# PCB-DISPARRAY4c.net
KiCad netlist of a schematic drawn in EAGLE
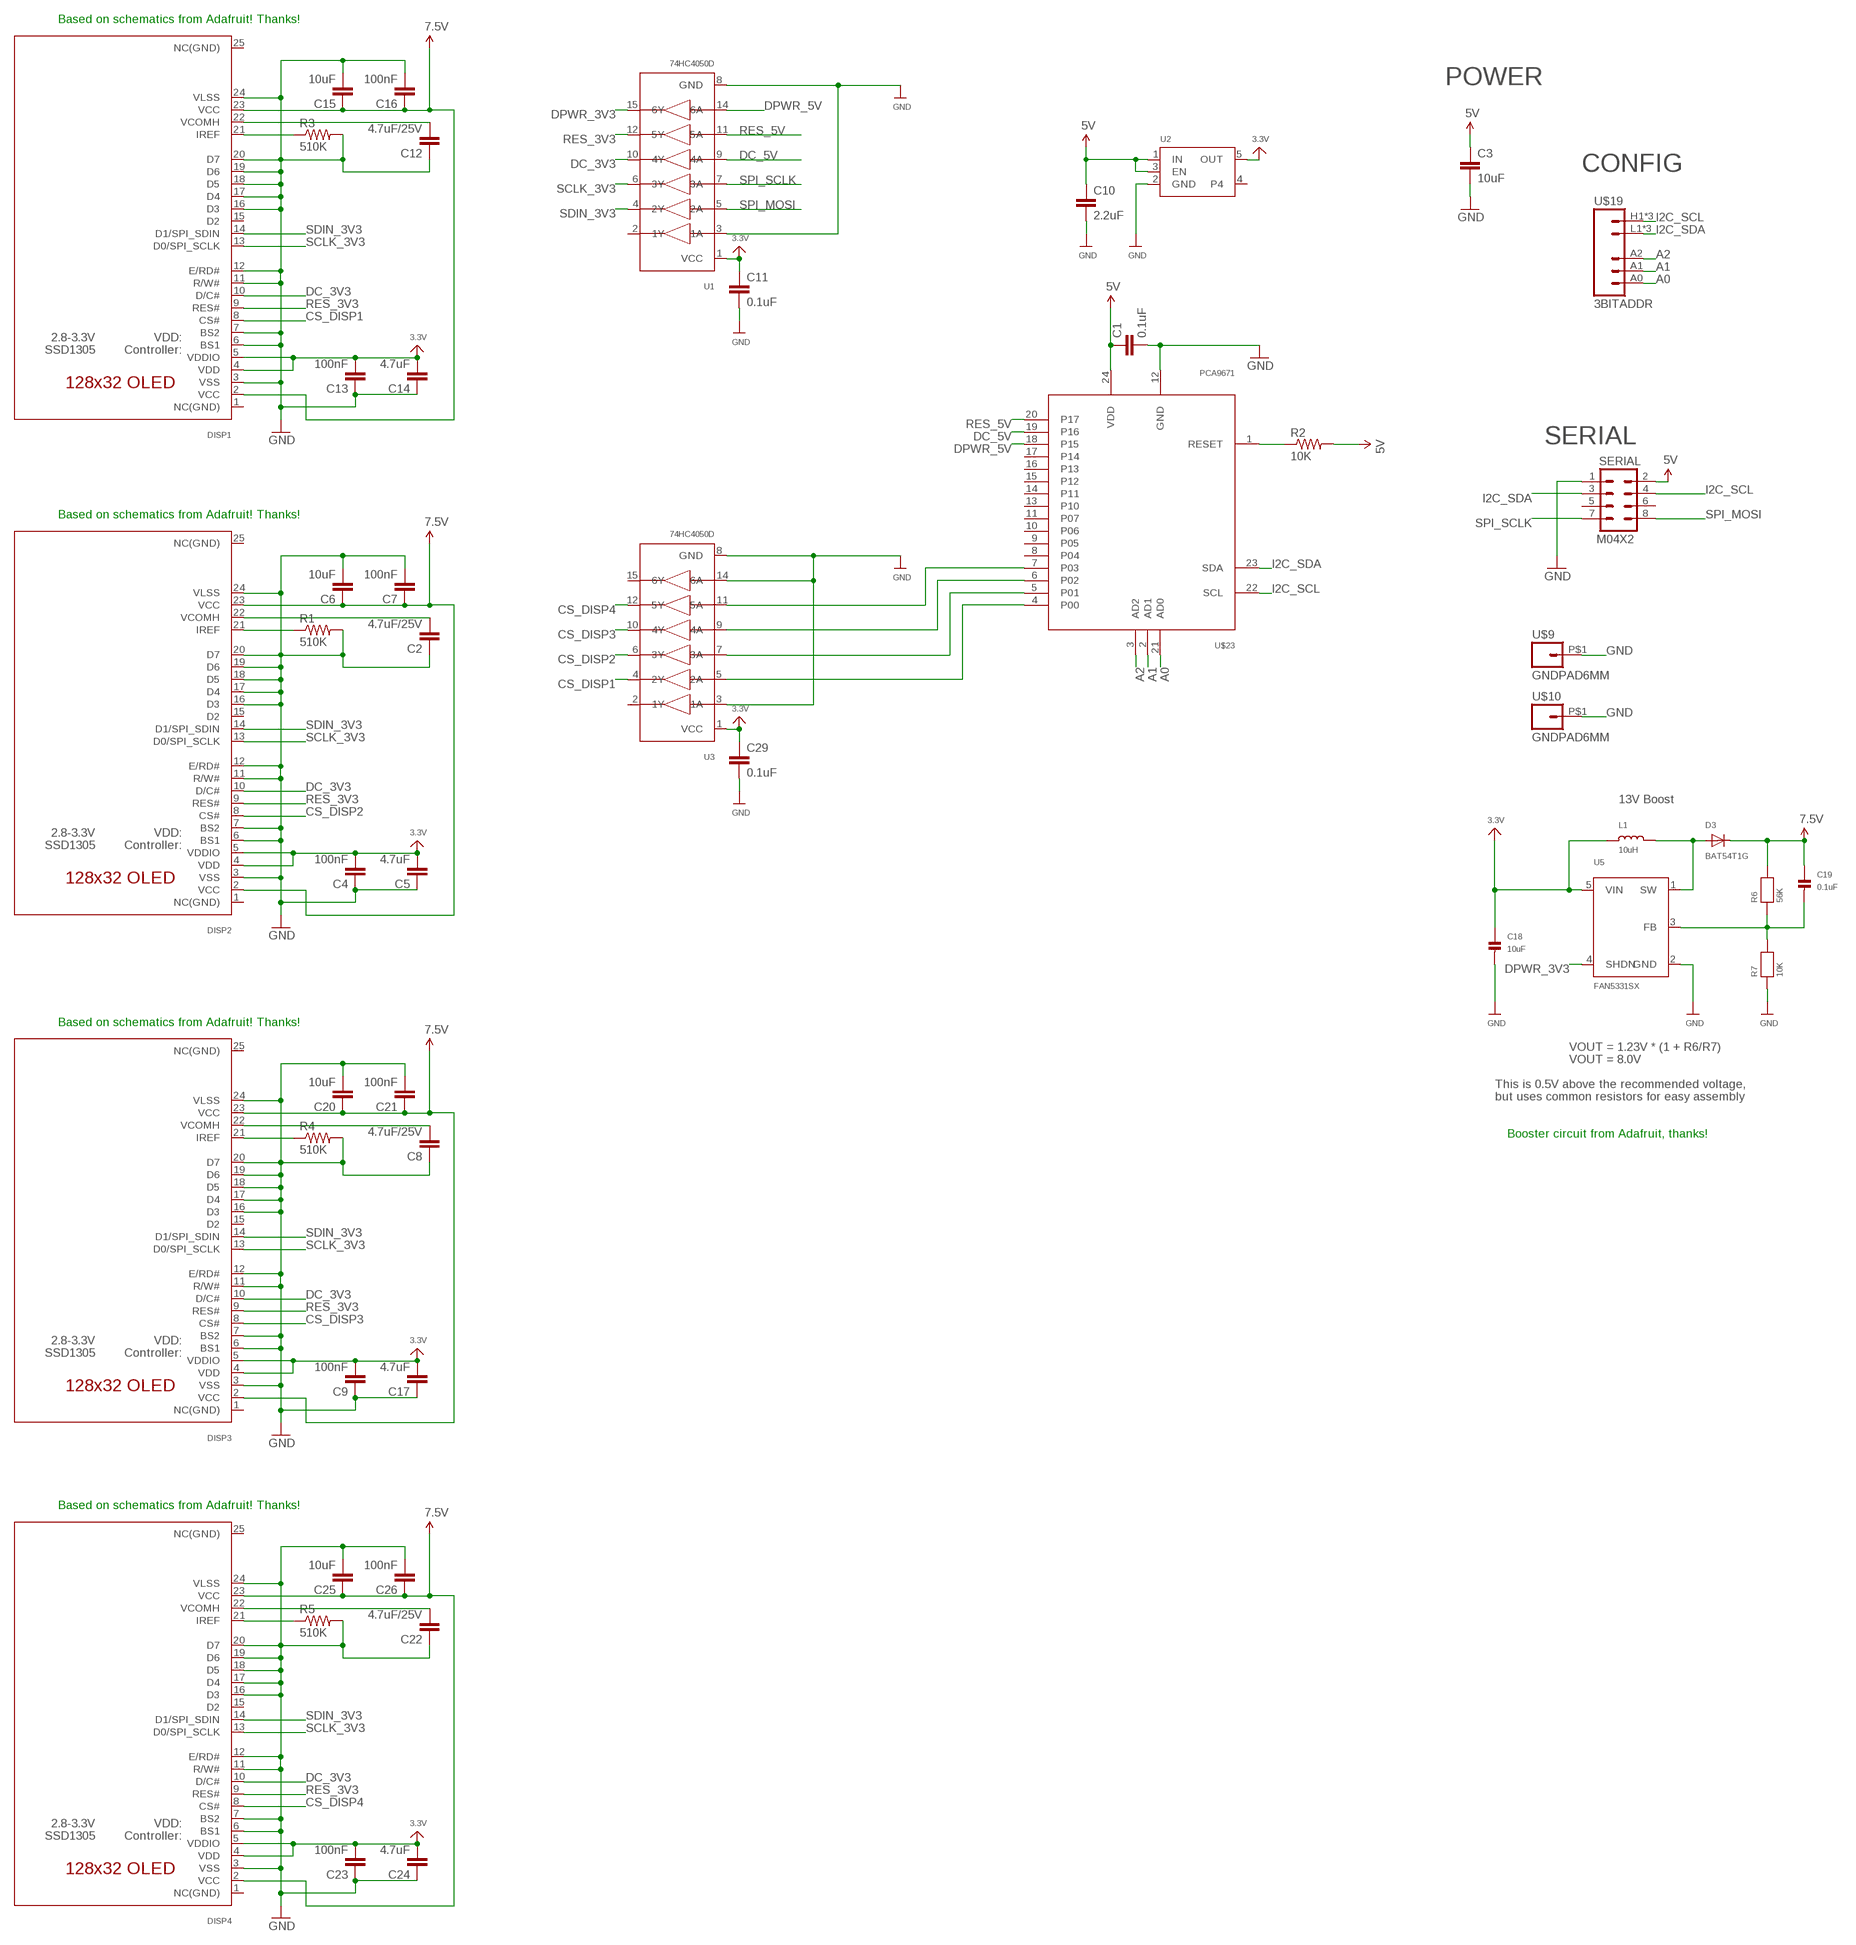
[diagram p0: schematic, sheet 1]

(export (version "E")
  (design (tool "Eeschema 10.0.6"))
  (components
    (comp (ref "C1")
      (value "0.1uF")
      (footprint "eagle-import:0603-CAP")
      (libsource (lib "eagle-import") (part "CAP0603-CAP"))
    )
    (comp (ref "C2")
      (value "4.7uF/25V")
      (footprint "eagle-import:0805")
      (libsource (lib "eagle-import") (part "CAP0805"))
    )
    (comp (ref "C3")
      (value "10uF")
      (footprint "eagle-import:0805")
      (libsource (lib "eagle-import") (part "CAP0805"))
    )
    (comp (ref "C4")
      (value "100nF")
      (footprint "eagle-import:0603-CAP")
      (libsource (lib "eagle-import") (part "CAP0603-CAP"))
    )
    (comp (ref "C5")
      (value "4.7uF")
      (footprint "eagle-import:0603-CAP")
      (libsource (lib "eagle-import") (part "CAP0603-CAP"))
    )
    (comp (ref "C6")
      (value "10uF")
      (footprint "eagle-import:0805")
      (libsource (lib "eagle-import") (part "CAP0805"))
    )
    (comp (ref "C7")
      (value "100nF")
      (footprint "eagle-import:0805")
      (libsource (lib "eagle-import") (part "CAP0805"))
    )
    (comp (ref "C8")
      (value "4.7uF/25V")
      (footprint "eagle-import:0805")
      (libsource (lib "eagle-import") (part "CAP0805"))
    )
    (comp (ref "C9")
      (value "100nF")
      (footprint "eagle-import:0603-CAP")
      (libsource (lib "eagle-import") (part "CAP0603-CAP"))
    )
    (comp (ref "C10")
      (value "2.2uF")
      (footprint "eagle-import:0603-CAP")
      (libsource (lib "eagle-import") (part "CAP0603-CAP"))
    )
    (comp (ref "C11")
      (value "0.1uF")
      (footprint "eagle-import:0603-CAP")
      (libsource (lib "eagle-import") (part "CAP0603-CAP"))
    )
    (comp (ref "C12")
      (value "4.7uF/25V")
      (footprint "eagle-import:0805")
      (libsource (lib "eagle-import") (part "CAP0805"))
    )
    (comp (ref "C13")
      (value "100nF")
      (footprint "eagle-import:0603-CAP")
      (libsource (lib "eagle-import") (part "CAP0603-CAP"))
    )
    (comp (ref "C14")
      (value "4.7uF")
      (footprint "eagle-import:0603-CAP")
      (libsource (lib "eagle-import") (part "CAP0603-CAP"))
    )
    (comp (ref "C15")
      (value "10uF")
      (footprint "eagle-import:0805")
      (libsource (lib "eagle-import") (part "CAP0805"))
    )
    (comp (ref "C16")
      (value "100nF")
      (footprint "eagle-import:0603-CAP")
      (libsource (lib "eagle-import") (part "CAP0603-CAP"))
    )
    (comp (ref "C17")
      (value "4.7uF")
      (footprint "eagle-import:0603-CAP")
      (libsource (lib "eagle-import") (part "CAP0603-CAP"))
    )
    (comp (ref "C18")
      (value "10uF")
      (footprint "eagle-import:0805")
      (libsource (lib "eagle-import") (part "CAP_CERAMIC0805"))
    )
    (comp (ref "C19")
      (value "0.1uF")
      (footprint "eagle-import:0603")
      (libsource (lib "eagle-import") (part "CAP_CERAMIC0603"))
    )
    (comp (ref "C20")
      (value "10uF")
      (footprint "eagle-import:0805")
      (libsource (lib "eagle-import") (part "CAP0805"))
    )
    (comp (ref "C21")
      (value "100nF")
      (footprint "eagle-import:0603-CAP")
      (libsource (lib "eagle-import") (part "CAP0603-CAP"))
    )
    (comp (ref "C22")
      (value "4.7uF/25V")
      (footprint "eagle-import:0805")
      (libsource (lib "eagle-import") (part "CAP0805"))
    )
    (comp (ref "C23")
      (value "100nF")
      (footprint "eagle-import:0603-CAP")
      (libsource (lib "eagle-import") (part "CAP0603-CAP"))
    )
    (comp (ref "C24")
      (value "4.7uF")
      (footprint "eagle-import:0603-CAP")
      (libsource (lib "eagle-import") (part "CAP0603-CAP"))
    )
    (comp (ref "C25")
      (value "10uF")
      (footprint "eagle-import:0805")
      (libsource (lib "eagle-import") (part "CAP0805"))
    )
    (comp (ref "C26")
      (value "100nF")
      (footprint "eagle-import:0603-CAP")
      (libsource (lib "eagle-import") (part "CAP0603-CAP"))
    )
    (comp (ref "C29")
      (value "0.1uF")
      (footprint "eagle-import:0603-CAP")
      (libsource (lib "eagle-import") (part "CAP0603-CAP"))
    )
    (comp (ref "D3")
      (value "BAT54T1G")
      (footprint "eagle-import:SOD-123")
      (libsource (lib "eagle-import") (part "DIODESOD-123"))
    )
    (comp (ref "DISP1")
      (value "ER-OLED0.91-2TOP")
      (footprint "eagle-import:ER_OLED0.91-2")
      (libsource (lib "eagle-import") (part "ER-OLED0.91-2TOP"))
    )
    (comp (ref "DISP2")
      (value "ER-OLED0.91-2TOP")
      (footprint "eagle-import:ER_OLED0.91-2")
      (libsource (lib "eagle-import") (part "ER-OLED0.91-2TOP"))
    )
    (comp (ref "DISP3")
      (value "ER-OLED0.91-2TOP")
      (footprint "eagle-import:ER_OLED0.91-2")
      (libsource (lib "eagle-import") (part "ER-OLED0.91-2TOP"))
    )
    (comp (ref "DISP4")
      (value "ER-OLED0.91-2TOP")
      (footprint "eagle-import:ER_OLED0.91-2")
      (libsource (lib "eagle-import") (part "ER-OLED0.91-2TOP"))
    )
    (comp (ref "L1")
      (value "10uH")
      (footprint "eagle-import:INDUCTOR_1007")
      (libsource (lib "eagle-import") (part "INDUCTOR"))
    )
    (comp (ref "R1")
      (value "510K")
      (footprint "eagle-import:0603-RES")
      (libsource (lib "eagle-import") (part "RESISTOR0603-RES"))
    )
    (comp (ref "R2")
      (value "10K")
      (footprint "eagle-import:0603-RES")
      (libsource (lib "eagle-import") (part "RESISTOR0603-RES"))
    )
    (comp (ref "R3")
      (value "510K")
      (footprint "eagle-import:0603-RES")
      (libsource (lib "eagle-import") (part "RESISTOR0603-RES"))
    )
    (comp (ref "R4")
      (value "510K")
      (footprint "eagle-import:0603-RES")
      (libsource (lib "eagle-import") (part "RESISTOR0603-RES"))
    )
    (comp (ref "R5")
      (value "510K")
      (footprint "eagle-import:0603-RES")
      (libsource (lib "eagle-import") (part "RESISTOR0603-RES"))
    )
    (comp (ref "R6")
      (value "56K")
      (footprint "eagle-import:0603")
      (libsource (lib "eagle-import") (part "RESISTOR0603"))
    )
    (comp (ref "R7")
      (value "10K")
      (footprint "eagle-import:0603")
      (libsource (lib "eagle-import") (part "RESISTOR0603"))
    )
    (comp (ref "SERIAL")
      (value "M04X2")
      (footprint "eagle-import:2X4")
      (libsource (lib "eagle-import") (part "M04X2"))
    )
    (comp (ref "U$9")
      (value "GNDPAD6MM")
      (footprint "eagle-import:3.2MMPAD6MM")
      (libsource (lib "eagle-import") (part "GNDPAD6MM"))
    )
    (comp (ref "U$10")
      (value "GNDPAD6MM")
      (footprint "eagle-import:3.2MMPAD6MM")
      (libsource (lib "eagle-import") (part "GNDPAD6MM"))
    )
    (comp (ref "U$19")
      (value "3BITADDR")
      (footprint "eagle-import:3BITADDR")
      (libsource (lib "eagle-import") (part "3BITADDR"))
    )
    (comp (ref "U$23")
      (value "PCA9671")
      (footprint "eagle-import:TSSOP24")
      (libsource (lib "eagle-import") (part "PCA9671"))
    )
    (comp (ref "U1")
      (value "74HC4050D")
      (footprint "eagle-import:TSSOP16")
      (libsource (lib "eagle-import") (part "74HC4050DTSSOP16"))
    )
    (comp (ref "U2")
      (value "VREG_SOT23-5")
      (footprint "eagle-import:SOT23-5")
      (libsource (lib "eagle-import") (part "VREG_SOT23-5"))
    )
    (comp (ref "U3")
      (value "74HC4050D")
      (footprint "eagle-import:TSSOP16")
      (libsource (lib "eagle-import") (part "74HC4050DTSSOP16"))
    )
    (comp (ref "U5")
      (value "FAN5331SX")
      (footprint "eagle-import:SOT23-5")
      (libsource (lib "eagle-import") (part "FAN5331"))
    )
  )
  (nets
    (net (code "1") (name "3.3V") (class "Default")
      (node (ref "C11") (pin "1") (pinfunction "1_1") (pintype "passive"))
      (node (ref "C13") (pin "2") (pinfunction "2_2") (pintype "passive"))
      (node (ref "C14") (pin "2") (pinfunction "2_2") (pintype "passive"))
      (node (ref "C17") (pin "2") (pinfunction "2_2") (pintype "passive"))
      (node (ref "C18") (pin "1") (pinfunction "P$1_1") (pintype "passive"))
      (node (ref "C23") (pin "2") (pinfunction "2_2") (pintype "passive"))
      (node (ref "C24") (pin "2") (pinfunction "2_2") (pintype "passive"))
      (node (ref "C29") (pin "1") (pinfunction "1_1") (pintype "passive"))
      (node (ref "C4") (pin "2") (pinfunction "2_2") (pintype "passive"))
      (node (ref "C5") (pin "2") (pinfunction "2_2") (pintype "passive"))
      (node (ref "C9") (pin "2") (pinfunction "2_2") (pintype "passive"))
      (node (ref "DISP1") (pin "4") (pinfunction "VDD_4") (pintype "power_in"))
      (node (ref "DISP1") (pin "5") (pinfunction "VDDIO_5") (pintype "power_in"))
      (node (ref "DISP2") (pin "4") (pinfunction "VDD_4") (pintype "power_in"))
      (node (ref "DISP2") (pin "5") (pinfunction "VDDIO_5") (pintype "power_in"))
      (node (ref "DISP3") (pin "4") (pinfunction "VDD_4") (pintype "power_in"))
      (node (ref "DISP3") (pin "5") (pinfunction "VDDIO_5") (pintype "power_in"))
      (node (ref "DISP4") (pin "4") (pinfunction "VDD_4") (pintype "power_in"))
      (node (ref "DISP4") (pin "5") (pinfunction "VDDIO_5") (pintype "power_in"))
      (node (ref "L1") (pin "P$1") (pinfunction "1_P$1") (pintype "passive"))
      (node (ref "U1") (pin "1") (pinfunction "VCC_1") (pintype "bidirectional"))
      (node (ref "U2") (pin "5") (pinfunction "OUT_5") (pintype "bidirectional"))
      (node (ref "U3") (pin "1") (pinfunction "VCC_1") (pintype "bidirectional"))
      (node (ref "U5") (pin "5") (pinfunction "VIN_5") (pintype "bidirectional"))
    )
    (net (code "2") (name "5V") (class "Default")
      (node (ref "C1") (pin "1") (pinfunction "1_1") (pintype "passive"))
      (node (ref "C10") (pin "1") (pinfunction "1_1") (pintype "passive"))
      (node (ref "C3") (pin "1") (pinfunction "1_1") (pintype "passive"))
      (node (ref "R2") (pin "2") (pinfunction "2_2") (pintype "passive"))
      (node (ref "SERIAL") (pin "2") (pinfunction "2_2") (pintype "passive"))
      (node (ref "U$23") (pin "24") (pinfunction "VDD_24") (pintype "power_in"))
      (node (ref "U2") (pin "1") (pinfunction "IN_1") (pintype "bidirectional"))
      (node (ref "U2") (pin "3") (pinfunction "EN_3") (pintype "bidirectional"))
    )
    (net (code "3") (name "7.5V") (class "Default")
      (node (ref "C15") (pin "1") (pinfunction "1_1") (pintype "passive"))
      (node (ref "C16") (pin "1") (pinfunction "1_1") (pintype "passive"))
      (node (ref "C19") (pin "1") (pinfunction "P$1_1") (pintype "passive"))
      (node (ref "C20") (pin "1") (pinfunction "1_1") (pintype "passive"))
      (node (ref "C21") (pin "1") (pinfunction "1_1") (pintype "passive"))
      (node (ref "C25") (pin "1") (pinfunction "1_1") (pintype "passive"))
      (node (ref "C26") (pin "1") (pinfunction "1_1") (pintype "passive"))
      (node (ref "C6") (pin "1") (pinfunction "1_1") (pintype "passive"))
      (node (ref "C7") (pin "1") (pinfunction "1_1") (pintype "passive"))
      (node (ref "D3") (pin "C") (pinfunction "C_C") (pintype "passive"))
      (node (ref "DISP1") (pin "2") (pinfunction "VCC_2") (pintype "power_in"))
      (node (ref "DISP1") (pin "23") (pinfunction "VCC_23") (pintype "power_in"))
      (node (ref "DISP2") (pin "2") (pinfunction "VCC_2") (pintype "power_in"))
      (node (ref "DISP2") (pin "23") (pinfunction "VCC_23") (pintype "power_in"))
      (node (ref "DISP3") (pin "2") (pinfunction "VCC_2") (pintype "power_in"))
      (node (ref "DISP3") (pin "23") (pinfunction "VCC_23") (pintype "power_in"))
      (node (ref "DISP4") (pin "2") (pinfunction "VCC_2") (pintype "power_in"))
      (node (ref "DISP4") (pin "23") (pinfunction "VCC_23") (pintype "power_in"))
      (node (ref "R6") (pin "2") (pinfunction "2_2") (pintype "passive"))
    )
    (net (code "4") (name "A0") (class "Default")
      (node (ref "U$19") (pin "A0") (pinfunction "A0_A0") (pintype "passive"))
      (node (ref "U$23") (pin "21") (pinfunction "AD0_21") (pintype "input"))
    )
    (net (code "5") (name "A1") (class "Default")
      (node (ref "U$19") (pin "A1") (pinfunction "A1_A1") (pintype "passive"))
      (node (ref "U$23") (pin "2") (pinfunction "AD1_2") (pintype "input"))
    )
    (net (code "6") (name "A2") (class "Default")
      (node (ref "U$19") (pin "A2") (pinfunction "A2_A2") (pintype "passive"))
      (node (ref "U$23") (pin "3") (pinfunction "AD2_3") (pintype "input"))
    )
    (net (code "7") (name "CS_DISP1") (class "Default")
      (node (ref "DISP1") (pin "8") (pinfunction "CS#_8") (pintype "input"))
      (node (ref "U3") (pin "4") (pinfunction "2Y_4") (pintype "bidirectional"))
    )
    (net (code "8") (name "CS_DISP2") (class "Default")
      (node (ref "DISP2") (pin "8") (pinfunction "CS#_8") (pintype "input"))
      (node (ref "U3") (pin "6") (pinfunction "3Y_6") (pintype "bidirectional"))
    )
    (net (code "9") (name "CS_DISP3") (class "Default")
      (node (ref "DISP3") (pin "8") (pinfunction "CS#_8") (pintype "input"))
      (node (ref "U3") (pin "10") (pinfunction "4Y_10") (pintype "bidirectional"))
    )
    (net (code "10") (name "CS_DISP4") (class "Default")
      (node (ref "DISP4") (pin "8") (pinfunction "CS#_8") (pintype "input"))
      (node (ref "U3") (pin "12") (pinfunction "5Y_12") (pintype "bidirectional"))
    )
    (net (code "11") (name "DC_3V3") (class "Default")
      (node (ref "DISP1") (pin "10") (pinfunction "D/C#_10") (pintype "input"))
      (node (ref "DISP2") (pin "10") (pinfunction "D/C#_10") (pintype "input"))
      (node (ref "DISP3") (pin "10") (pinfunction "D/C#_10") (pintype "input"))
      (node (ref "DISP4") (pin "10") (pinfunction "D/C#_10") (pintype "input"))
      (node (ref "U1") (pin "10") (pinfunction "4Y_10") (pintype "bidirectional"))
    )
    (net (code "12") (name "DC_5V") (class "Default")
      (node (ref "U$23") (pin "19") (pinfunction "P16_19") (pintype "output"))
      (node (ref "U1") (pin "9") (pinfunction "4A_9") (pintype "bidirectional"))
    )
    (net (code "13") (name "DPWR_3V3") (class "Default")
      (node (ref "U1") (pin "15") (pinfunction "6Y_15") (pintype "bidirectional"))
      (node (ref "U5") (pin "4") (pinfunction "SHDN_4") (pintype "bidirectional"))
    )
    (net (code "14") (name "DPWR_5V") (class "Default")
      (node (ref "U$23") (pin "18") (pinfunction "P15_18") (pintype "output"))
      (node (ref "U1") (pin "14") (pinfunction "6A_14") (pintype "bidirectional"))
    )
    (net (code "15") (name "GND") (class "Default")
      (node (ref "C1") (pin "2") (pinfunction "2_2") (pintype "passive"))
      (node (ref "C10") (pin "2") (pinfunction "2_2") (pintype "passive"))
      (node (ref "C11") (pin "2") (pinfunction "2_2") (pintype "passive"))
      (node (ref "C12") (pin "1") (pinfunction "1_1") (pintype "passive"))
      (node (ref "C13") (pin "1") (pinfunction "1_1") (pintype "passive"))
      (node (ref "C14") (pin "1") (pinfunction "1_1") (pintype "passive"))
      (node (ref "C15") (pin "2") (pinfunction "2_2") (pintype "passive"))
      (node (ref "C16") (pin "2") (pinfunction "2_2") (pintype "passive"))
      (node (ref "C17") (pin "1") (pinfunction "1_1") (pintype "passive"))
      (node (ref "C18") (pin "2") (pinfunction "P$2_2") (pintype "passive"))
      (node (ref "C2") (pin "1") (pinfunction "1_1") (pintype "passive"))
      (node (ref "C20") (pin "2") (pinfunction "2_2") (pintype "passive"))
      (node (ref "C21") (pin "2") (pinfunction "2_2") (pintype "passive"))
      (node (ref "C22") (pin "1") (pinfunction "1_1") (pintype "passive"))
      (node (ref "C23") (pin "1") (pinfunction "1_1") (pintype "passive"))
      (node (ref "C24") (pin "1") (pinfunction "1_1") (pintype "passive"))
      (node (ref "C25") (pin "2") (pinfunction "2_2") (pintype "passive"))
      (node (ref "C26") (pin "2") (pinfunction "2_2") (pintype "passive"))
      (node (ref "C29") (pin "2") (pinfunction "2_2") (pintype "passive"))
      (node (ref "C3") (pin "2") (pinfunction "2_2") (pintype "passive"))
      (node (ref "C4") (pin "1") (pinfunction "1_1") (pintype "passive"))
      (node (ref "C5") (pin "1") (pinfunction "1_1") (pintype "passive"))
      (node (ref "C6") (pin "2") (pinfunction "2_2") (pintype "passive"))
      (node (ref "C7") (pin "2") (pinfunction "2_2") (pintype "passive"))
      (node (ref "C8") (pin "1") (pinfunction "1_1") (pintype "passive"))
      (node (ref "C9") (pin "1") (pinfunction "1_1") (pintype "passive"))
      (node (ref "DISP1") (pin "11") (pinfunction "R/W#_11") (pintype "input"))
      (node (ref "DISP1") (pin "12") (pinfunction "E/RD#_12") (pintype "input"))
      (node (ref "DISP1") (pin "16") (pinfunction "D3_16") (pintype "bidirectional"))
      (node (ref "DISP1") (pin "17") (pinfunction "D4_17") (pintype "bidirectional"))
      (node (ref "DISP1") (pin "18") (pinfunction "D5_18") (pintype "bidirectional"))
      (node (ref "DISP1") (pin "19") (pinfunction "D6_19") (pintype "bidirectional"))
      (node (ref "DISP1") (pin "20") (pinfunction "D7_20") (pintype "bidirectional"))
      (node (ref "DISP1") (pin "24") (pinfunction "VLSS_24") (pintype "power_in"))
      (node (ref "DISP1") (pin "3") (pinfunction "VSS_3") (pintype "power_in"))
      (node (ref "DISP1") (pin "6") (pinfunction "BS1_6") (pintype "input"))
      (node (ref "DISP1") (pin "7") (pinfunction "BS2_7") (pintype "input"))
      (node (ref "DISP2") (pin "11") (pinfunction "R/W#_11") (pintype "input"))
      (node (ref "DISP2") (pin "12") (pinfunction "E/RD#_12") (pintype "input"))
      (node (ref "DISP2") (pin "16") (pinfunction "D3_16") (pintype "bidirectional"))
      (node (ref "DISP2") (pin "17") (pinfunction "D4_17") (pintype "bidirectional"))
      (node (ref "DISP2") (pin "18") (pinfunction "D5_18") (pintype "bidirectional"))
      (node (ref "DISP2") (pin "19") (pinfunction "D6_19") (pintype "bidirectional"))
      (node (ref "DISP2") (pin "20") (pinfunction "D7_20") (pintype "bidirectional"))
      (node (ref "DISP2") (pin "24") (pinfunction "VLSS_24") (pintype "power_in"))
      (node (ref "DISP2") (pin "3") (pinfunction "VSS_3") (pintype "power_in"))
      (node (ref "DISP2") (pin "6") (pinfunction "BS1_6") (pintype "input"))
      (node (ref "DISP2") (pin "7") (pinfunction "BS2_7") (pintype "input"))
      (node (ref "DISP3") (pin "11") (pinfunction "R/W#_11") (pintype "input"))
      (node (ref "DISP3") (pin "12") (pinfunction "E/RD#_12") (pintype "input"))
      (node (ref "DISP3") (pin "16") (pinfunction "D3_16") (pintype "bidirectional"))
      (node (ref "DISP3") (pin "17") (pinfunction "D4_17") (pintype "bidirectional"))
      (node (ref "DISP3") (pin "18") (pinfunction "D5_18") (pintype "bidirectional"))
      (node (ref "DISP3") (pin "19") (pinfunction "D6_19") (pintype "bidirectional"))
      (node (ref "DISP3") (pin "20") (pinfunction "D7_20") (pintype "bidirectional"))
      (node (ref "DISP3") (pin "24") (pinfunction "VLSS_24") (pintype "power_in"))
      (node (ref "DISP3") (pin "3") (pinfunction "VSS_3") (pintype "power_in"))
      (node (ref "DISP3") (pin "6") (pinfunction "BS1_6") (pintype "input"))
      (node (ref "DISP3") (pin "7") (pinfunction "BS2_7") (pintype "input"))
      (node (ref "DISP4") (pin "11") (pinfunction "R/W#_11") (pintype "input"))
      (node (ref "DISP4") (pin "12") (pinfunction "E/RD#_12") (pintype "input"))
      (node (ref "DISP4") (pin "16") (pinfunction "D3_16") (pintype "bidirectional"))
      (node (ref "DISP4") (pin "17") (pinfunction "D4_17") (pintype "bidirectional"))
      (node (ref "DISP4") (pin "18") (pinfunction "D5_18") (pintype "bidirectional"))
      (node (ref "DISP4") (pin "19") (pinfunction "D6_19") (pintype "bidirectional"))
      (node (ref "DISP4") (pin "20") (pinfunction "D7_20") (pintype "bidirectional"))
      (node (ref "DISP4") (pin "24") (pinfunction "VLSS_24") (pintype "power_in"))
      (node (ref "DISP4") (pin "3") (pinfunction "VSS_3") (pintype "power_in"))
      (node (ref "DISP4") (pin "6") (pinfunction "BS1_6") (pintype "input"))
      (node (ref "DISP4") (pin "7") (pinfunction "BS2_7") (pintype "input"))
      (node (ref "R1") (pin "2") (pinfunction "2_2") (pintype "passive"))
      (node (ref "R3") (pin "2") (pinfunction "2_2") (pintype "passive"))
      (node (ref "R4") (pin "2") (pinfunction "2_2") (pintype "passive"))
      (node (ref "R5") (pin "2") (pinfunction "2_2") (pintype "passive"))
      (node (ref "R7") (pin "1") (pinfunction "1_1") (pintype "passive"))
      (node (ref "SERIAL") (pin "1") (pinfunction "1_1") (pintype "passive"))
      (node (ref "U$10") (pin "P$1") (pinfunction "1_P$1") (pintype "passive"))
      (node (ref "U$23") (pin "12") (pinfunction "GND_12") (pintype "power_in"))
      (node (ref "U$9") (pin "P$1") (pinfunction "1_P$1") (pintype "passive"))
      (node (ref "U1") (pin "3") (pinfunction "1A_3") (pintype "bidirectional"))
      (node (ref "U1") (pin "8") (pinfunction "GND_8") (pintype "bidirectional"))
      (node (ref "U2") (pin "2") (pinfunction "GND_2") (pintype "bidirectional"))
      (node (ref "U3") (pin "14") (pinfunction "6A_14") (pintype "bidirectional"))
      (node (ref "U3") (pin "3") (pinfunction "1A_3") (pintype "bidirectional"))
      (node (ref "U3") (pin "8") (pinfunction "GND_8") (pintype "bidirectional"))
      (node (ref "U5") (pin "2") (pinfunction "GND_2") (pintype "bidirectional"))
    )
    (net (code "16") (name "I2C_SCL") (class "Default")
      (node (ref "SERIAL") (pin "4") (pinfunction "4_4") (pintype "passive"))
      (node (ref "U$19") (pin "H1") (pinfunction "VCC_H1") (pintype "passive"))
      (node (ref "U$19") (pin "H2") (pinfunction "VCC_H2") (pintype "passive"))
      (node (ref "U$19") (pin "H3") (pinfunction "VCC_H3") (pintype "passive"))
      (node (ref "U$23") (pin "22") (pinfunction "SCL_22") (pintype "input"))
    )
    (net (code "17") (name "I2C_SDA") (class "Default")
      (node (ref "SERIAL") (pin "3") (pinfunction "3_3") (pintype "passive"))
      (node (ref "U$19") (pin "L1") (pinfunction "GND_L1") (pintype "passive"))
      (node (ref "U$19") (pin "L2") (pinfunction "GND_L2") (pintype "passive"))
      (node (ref "U$19") (pin "L3") (pinfunction "GND_L3") (pintype "passive"))
      (node (ref "U$23") (pin "23") (pinfunction "SDA_23") (pintype "input"))
    )
    (net (code "18") (name "Net-(C19-P$2)") (class "Default")
      (node (ref "C19") (pin "2") (pinfunction "P$2_2") (pintype "passive"))
      (node (ref "R6") (pin "1") (pinfunction "1_1") (pintype "passive"))
      (node (ref "R7") (pin "2") (pinfunction "2_2") (pintype "passive"))
      (node (ref "U5") (pin "3") (pinfunction "FB_3") (pintype "bidirectional"))
    )
    (net (code "19") (name "Net-(DISP1-IREF)") (class "Default")
      (node (ref "DISP1") (pin "21") (pinfunction "IREF_21") (pintype "input"))
      (node (ref "R3") (pin "1") (pinfunction "1_1") (pintype "passive"))
    )
    (net (code "20") (name "Net-(DISP1-VCOMH)") (class "Default")
      (node (ref "C12") (pin "2") (pinfunction "2_2") (pintype "passive"))
      (node (ref "DISP1") (pin "22") (pinfunction "VCOMH_22") (pintype "output"))
    )
    (net (code "21") (name "Net-(DISP2-IREF)") (class "Default")
      (node (ref "DISP2") (pin "21") (pinfunction "IREF_21") (pintype "input"))
      (node (ref "R1") (pin "1") (pinfunction "1_1") (pintype "passive"))
    )
    (net (code "22") (name "Net-(DISP2-VCOMH)") (class "Default")
      (node (ref "C2") (pin "2") (pinfunction "2_2") (pintype "passive"))
      (node (ref "DISP2") (pin "22") (pinfunction "VCOMH_22") (pintype "output"))
    )
    (net (code "23") (name "Net-(DISP3-IREF)") (class "Default")
      (node (ref "DISP3") (pin "21") (pinfunction "IREF_21") (pintype "input"))
      (node (ref "R4") (pin "1") (pinfunction "1_1") (pintype "passive"))
    )
    (net (code "24") (name "Net-(DISP3-VCOMH)") (class "Default")
      (node (ref "C8") (pin "2") (pinfunction "2_2") (pintype "passive"))
      (node (ref "DISP3") (pin "22") (pinfunction "VCOMH_22") (pintype "output"))
    )
    (net (code "25") (name "Net-(DISP4-IREF)") (class "Default")
      (node (ref "DISP4") (pin "21") (pinfunction "IREF_21") (pintype "input"))
      (node (ref "R5") (pin "1") (pinfunction "1_1") (pintype "passive"))
    )
    (net (code "26") (name "Net-(DISP4-VCOMH)") (class "Default")
      (node (ref "C22") (pin "2") (pinfunction "2_2") (pintype "passive"))
      (node (ref "DISP4") (pin "22") (pinfunction "VCOMH_22") (pintype "output"))
    )
    (net (code "27") (name "Net-(L1-2)") (class "Default")
      (node (ref "D3") (pin "A") (pinfunction "A_A") (pintype "passive"))
      (node (ref "L1") (pin "P$2") (pinfunction "2_P$2") (pintype "passive"))
      (node (ref "U5") (pin "1") (pinfunction "SW_1") (pintype "bidirectional"))
    )
    (net (code "28") (name "Net-(U$23-P00)") (class "Default")
      (node (ref "U$23") (pin "4") (pinfunction "P00_4") (pintype "output"))
      (node (ref "U3") (pin "5") (pinfunction "2A_5") (pintype "bidirectional"))
    )
    (net (code "29") (name "Net-(U$23-P01)") (class "Default")
      (node (ref "U$23") (pin "5") (pinfunction "P01_5") (pintype "output"))
      (node (ref "U3") (pin "7") (pinfunction "3A_7") (pintype "bidirectional"))
    )
    (net (code "30") (name "Net-(U$23-P02)") (class "Default")
      (node (ref "U$23") (pin "6") (pinfunction "P02_6") (pintype "output"))
      (node (ref "U3") (pin "9") (pinfunction "4A_9") (pintype "bidirectional"))
    )
    (net (code "31") (name "Net-(U$23-P03)") (class "Default")
      (node (ref "U$23") (pin "7") (pinfunction "P03_7") (pintype "output"))
      (node (ref "U3") (pin "11") (pinfunction "5A_11") (pintype "bidirectional"))
    )
    (net (code "32") (name "Net-(U$23-RESET)") (class "Default")
      (node (ref "R2") (pin "1") (pinfunction "1_1") (pintype "passive"))
      (node (ref "U$23") (pin "1") (pinfunction "RESET_1") (pintype "input"))
    )
    (net (code "33") (name "RES_3V3") (class "Default")
      (node (ref "DISP1") (pin "9") (pinfunction "RES#_9") (pintype "input"))
      (node (ref "DISP2") (pin "9") (pinfunction "RES#_9") (pintype "input"))
      (node (ref "DISP3") (pin "9") (pinfunction "RES#_9") (pintype "input"))
      (node (ref "DISP4") (pin "9") (pinfunction "RES#_9") (pintype "input"))
      (node (ref "U1") (pin "12") (pinfunction "5Y_12") (pintype "bidirectional"))
    )
    (net (code "34") (name "RES_5V") (class "Default")
      (node (ref "U$23") (pin "20") (pinfunction "P17_20") (pintype "output"))
      (node (ref "U1") (pin "11") (pinfunction "5A_11") (pintype "bidirectional"))
    )
    (net (code "35") (name "SCLK_3V3") (class "Default")
      (node (ref "DISP1") (pin "13") (pinfunction "D0/SPI_SCLK_13") (pintype "bidirectional"))
      (node (ref "DISP2") (pin "13") (pinfunction "D0/SPI_SCLK_13") (pintype "bidirectional"))
      (node (ref "DISP3") (pin "13") (pinfunction "D0/SPI_SCLK_13") (pintype "bidirectional"))
      (node (ref "DISP4") (pin "13") (pinfunction "D0/SPI_SCLK_13") (pintype "bidirectional"))
      (node (ref "U1") (pin "6") (pinfunction "3Y_6") (pintype "bidirectional"))
    )
    (net (code "36") (name "SDIN_3V3") (class "Default")
      (node (ref "DISP1") (pin "14") (pinfunction "D1/SPI_SDIN_14") (pintype "bidirectional"))
      (node (ref "DISP2") (pin "14") (pinfunction "D1/SPI_SDIN_14") (pintype "bidirectional"))
      (node (ref "DISP3") (pin "14") (pinfunction "D1/SPI_SDIN_14") (pintype "bidirectional"))
      (node (ref "DISP4") (pin "14") (pinfunction "D1/SPI_SDIN_14") (pintype "bidirectional"))
      (node (ref "U1") (pin "4") (pinfunction "2Y_4") (pintype "bidirectional"))
    )
    (net (code "37") (name "SPI_MOSI") (class "Default")
      (node (ref "SERIAL") (pin "8") (pinfunction "8_8") (pintype "passive"))
      (node (ref "U1") (pin "5") (pinfunction "2A_5") (pintype "bidirectional"))
    )
    (net (code "38") (name "SPI_SCLK") (class "Default")
      (node (ref "SERIAL") (pin "7") (pinfunction "7_7") (pintype "passive"))
      (node (ref "U1") (pin "7") (pinfunction "3A_7") (pintype "bidirectional"))
    )
    (net (code "39") (name "unconnected-(DISP1-D2-Pad15)") (class "Default")
      (node (ref "DISP1") (pin "15") (pinfunction "D2_15") (pintype "bidirectional"))
    )
    (net (code "40") (name "unconnected-(DISP1-NC(GND)-Pad1)") (class "Default")
      (node (ref "DISP1") (pin "1") (pinfunction "NC(GND)_1") (pintype "input"))
    )
    (net (code "41") (name "unconnected-(DISP1-NC(GND)-Pad25)") (class "Default")
      (node (ref "DISP1") (pin "25") (pinfunction "NC(GND)_25") (pintype "input"))
    )
    (net (code "42") (name "unconnected-(DISP2-D2-Pad15)") (class "Default")
      (node (ref "DISP2") (pin "15") (pinfunction "D2_15") (pintype "bidirectional"))
    )
    (net (code "43") (name "unconnected-(DISP2-NC(GND)-Pad1)") (class "Default")
      (node (ref "DISP2") (pin "1") (pinfunction "NC(GND)_1") (pintype "input"))
    )
    (net (code "44") (name "unconnected-(DISP2-NC(GND)-Pad25)") (class "Default")
      (node (ref "DISP2") (pin "25") (pinfunction "NC(GND)_25") (pintype "input"))
    )
    (net (code "45") (name "unconnected-(DISP3-D2-Pad15)") (class "Default")
      (node (ref "DISP3") (pin "15") (pinfunction "D2_15") (pintype "bidirectional"))
    )
    (net (code "46") (name "unconnected-(DISP3-NC(GND)-Pad1)") (class "Default")
      (node (ref "DISP3") (pin "1") (pinfunction "NC(GND)_1") (pintype "input"))
    )
    (net (code "47") (name "unconnected-(DISP3-NC(GND)-Pad25)") (class "Default")
      (node (ref "DISP3") (pin "25") (pinfunction "NC(GND)_25") (pintype "input"))
    )
    (net (code "48") (name "unconnected-(DISP4-D2-Pad15)") (class "Default")
      (node (ref "DISP4") (pin "15") (pinfunction "D2_15") (pintype "bidirectional"))
    )
    (net (code "49") (name "unconnected-(DISP4-NC(GND)-Pad1)") (class "Default")
      (node (ref "DISP4") (pin "1") (pinfunction "NC(GND)_1") (pintype "input"))
    )
    (net (code "50") (name "unconnected-(DISP4-NC(GND)-Pad25)") (class "Default")
      (node (ref "DISP4") (pin "25") (pinfunction "NC(GND)_25") (pintype "input"))
    )
    (net (code "51") (name "unconnected-(SERIAL-Pad5)") (class "Default")
      (node (ref "SERIAL") (pin "5") (pinfunction "5_5") (pintype "passive"))
    )
    (net (code "52") (name "unconnected-(SERIAL-Pad6)") (class "Default")
      (node (ref "SERIAL") (pin "6") (pinfunction "6_6") (pintype "passive"))
    )
    (net (code "53") (name "unconnected-(U$23-P04-Pad8)") (class "Default")
      (node (ref "U$23") (pin "8") (pinfunction "P04_8") (pintype "output"))
    )
    (net (code "54") (name "unconnected-(U$23-P05-Pad9)") (class "Default")
      (node (ref "U$23") (pin "9") (pinfunction "P05_9") (pintype "output"))
    )
    (net (code "55") (name "unconnected-(U$23-P06-Pad10)") (class "Default")
      (node (ref "U$23") (pin "10") (pinfunction "P06_10") (pintype "output"))
    )
    (net (code "56") (name "unconnected-(U$23-P07-Pad11)") (class "Default")
      (node (ref "U$23") (pin "11") (pinfunction "P07_11") (pintype "output"))
    )
    (net (code "57") (name "unconnected-(U$23-P10-Pad13)") (class "Default")
      (node (ref "U$23") (pin "13") (pinfunction "P10_13") (pintype "output"))
    )
    (net (code "58") (name "unconnected-(U$23-P11-Pad14)") (class "Default")
      (node (ref "U$23") (pin "14") (pinfunction "P11_14") (pintype "output"))
    )
    (net (code "59") (name "unconnected-(U$23-P12-Pad15)") (class "Default")
      (node (ref "U$23") (pin "15") (pinfunction "P12_15") (pintype "output"))
    )
    (net (code "60") (name "unconnected-(U$23-P13-Pad16)") (class "Default")
      (node (ref "U$23") (pin "16") (pinfunction "P13_16") (pintype "output"))
    )
    (net (code "61") (name "unconnected-(U$23-P14-Pad17)") (class "Default")
      (node (ref "U$23") (pin "17") (pinfunction "P14_17") (pintype "output"))
    )
    (net (code "62") (name "unconnected-(U1-1Y-Pad2)") (class "Default")
      (node (ref "U1") (pin "2") (pinfunction "1Y_2") (pintype "bidirectional"))
    )
    (net (code "63") (name "unconnected-(U2-P4-Pad4)") (class "Default")
      (node (ref "U2") (pin "4") (pinfunction "P4_4") (pintype "bidirectional"))
    )
    (net (code "64") (name "unconnected-(U3-1Y-Pad2)") (class "Default")
      (node (ref "U3") (pin "2") (pinfunction "1Y_2") (pintype "bidirectional"))
    )
    (net (code "65") (name "unconnected-(U3-6Y-Pad15)") (class "Default")
      (node (ref "U3") (pin "15") (pinfunction "6Y_15") (pintype "bidirectional"))
    )
  )
)
